# isl-test.net
KiCad netlist of a schematic drawn in EAGLE
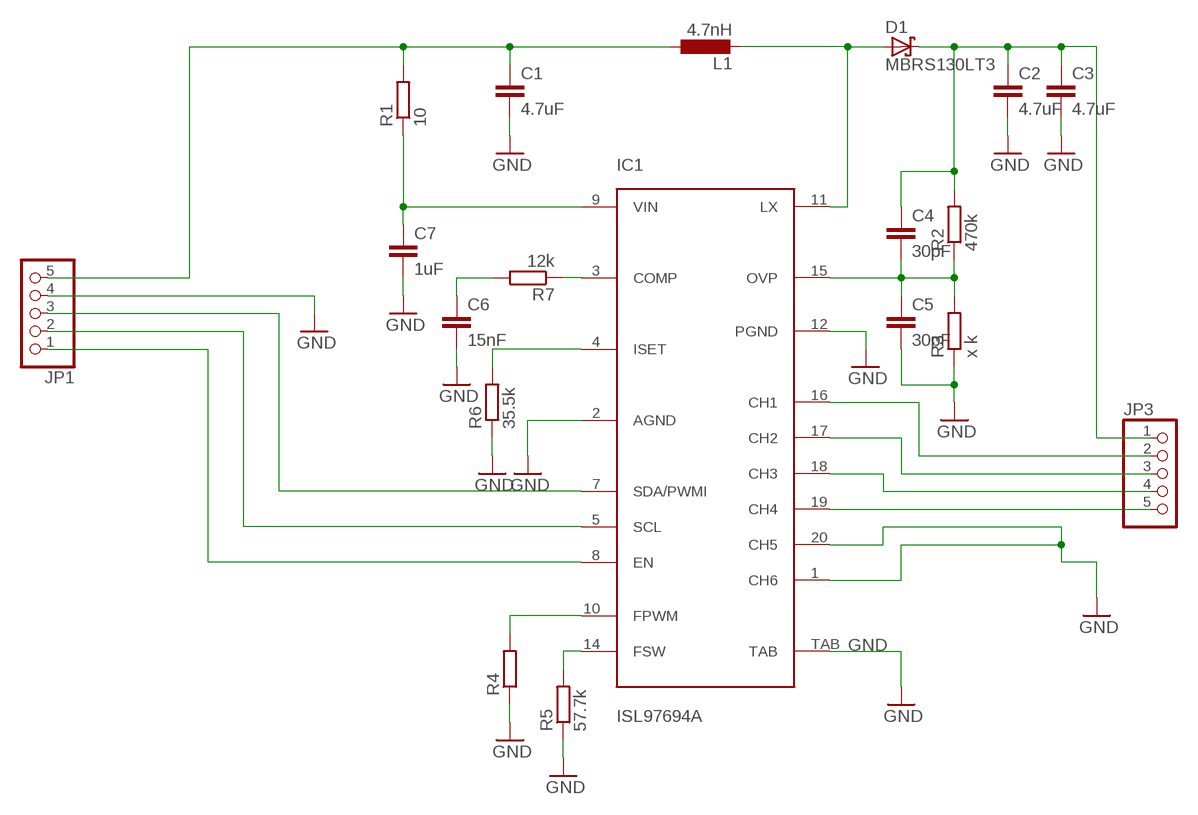
[diagram p0: schematic, sheet 1]

(export (version "E")
  (design (tool "Eeschema 10.0.6"))
  (components
    (comp (ref "C1")
      (value "4.7uF")
      (footprint "eagle-import:C0805")
      (libsource (lib "eagle-import") (part "C-EUC0805"))
    )
    (comp (ref "C2")
      (value "4.7uF")
      (footprint "eagle-import:C0805")
      (libsource (lib "eagle-import") (part "C-EUC0805"))
    )
    (comp (ref "C3")
      (value "4.7uF")
      (footprint "eagle-import:C0805")
      (libsource (lib "eagle-import") (part "C-EUC0805"))
    )
    (comp (ref "C4")
      (value "30pF")
      (footprint "eagle-import:C0603")
      (libsource (lib "eagle-import") (part "C-EUC0603"))
    )
    (comp (ref "C5")
      (value "30pF")
      (footprint "eagle-import:C0603")
      (libsource (lib "eagle-import") (part "C-EUC0603"))
    )
    (comp (ref "C6")
      (value "15nF")
      (footprint "eagle-import:C0603")
      (libsource (lib "eagle-import") (part "C-EUC0603"))
    )
    (comp (ref "C7")
      (value "1uF")
      (footprint "eagle-import:C0603")
      (libsource (lib "eagle-import") (part "C-EUC0603"))
    )
    (comp (ref "D1")
      (value "MBRS130LT3")
      (footprint "eagle-import:SMB")
      (libsource (lib "eagle-import") (part "MBRS130LT3"))
    )
    (comp (ref "IC1")
      (value "ISL97694A")
      (footprint "eagle-import:TQFN-20")
      (libsource (lib "eagle-import") (part "ISL97694A"))
    )
    (comp (ref "JP1")
      (value "PINHD-1X5")
      (footprint "eagle-import:1X05")
      (libsource (lib "eagle-import") (part "PINHD-1X5"))
    )
    (comp (ref "JP3")
      (value "PINHD-1X5")
      (footprint "eagle-import:1X05")
      (libsource (lib "eagle-import") (part "PINHD-1X5"))
    )
    (comp (ref "L1")
      (value "4.7nH")
      (footprint "eagle-import:L1812")
      (libsource (lib "eagle-import") (part "L-EUL1812"))
    )
    (comp (ref "R1")
      (value "10")
      (footprint "eagle-import:R0603")
      (libsource (lib "eagle-import") (part "R-EU_R0603"))
    )
    (comp (ref "R2")
      (value "470k")
      (footprint "eagle-import:R0603")
      (libsource (lib "eagle-import") (part "R-EU_R0603"))
    )
    (comp (ref "R3")
      (value "x k")
      (footprint "eagle-import:R0603")
      (libsource (lib "eagle-import") (part "R-EU_R0603"))
    )
    (comp (ref "R4")
      (value "R-EU_R0603")
      (footprint "eagle-import:R0603")
      (libsource (lib "eagle-import") (part "R-EU_R0603"))
    )
    (comp (ref "R5")
      (value "57.7k")
      (footprint "eagle-import:R0603")
      (libsource (lib "eagle-import") (part "R-EU_R0603"))
    )
    (comp (ref "R6")
      (value "35.5k")
      (footprint "eagle-import:R0603")
      (libsource (lib "eagle-import") (part "R-EU_R0603"))
    )
    (comp (ref "R7")
      (value "12k")
      (footprint "eagle-import:R0603")
      (libsource (lib "eagle-import") (part "R-EU_R0603"))
    )
  )
  (nets
    (net (code "1") (name "GND") (class "Default")
      (node (ref "C1") (pin "2") (pinfunction "2_2") (pintype "passive"))
      (node (ref "C2") (pin "2") (pinfunction "2_2") (pintype "passive"))
      (node (ref "C3") (pin "2") (pinfunction "2_2") (pintype "passive"))
      (node (ref "C5") (pin "2") (pinfunction "2_2") (pintype "passive"))
      (node (ref "C6") (pin "2") (pinfunction "2_2") (pintype "passive"))
      (node (ref "C7") (pin "2") (pinfunction "2_2") (pintype "passive"))
      (node (ref "IC1") (pin "1") (pinfunction "CH6_1") (pintype "input"))
      (node (ref "IC1") (pin "12") (pinfunction "PGND_12") (pintype "power_in"))
      (node (ref "IC1") (pin "2") (pinfunction "AGND_2") (pintype "power_in"))
      (node (ref "IC1") (pin "20") (pinfunction "CH5_20") (pintype "input"))
      (node (ref "IC1") (pin "TAB") (pinfunction "TAB_TAB") (pintype "power_in"))
      (node (ref "JP1") (pin "4") (pinfunction "4_4") (pintype "passive"))
      (node (ref "R3") (pin "1") (pinfunction "1_1") (pintype "passive"))
      (node (ref "R4") (pin "1") (pinfunction "1_1") (pintype "passive"))
      (node (ref "R5") (pin "1") (pinfunction "1_1") (pintype "passive"))
      (node (ref "R6") (pin "1") (pinfunction "1_1") (pintype "passive"))
    )
    (net (code "2") (name "Net-(C1-Pad1)") (class "Default")
      (node (ref "C1") (pin "1") (pinfunction "1_1") (pintype "passive"))
      (node (ref "JP1") (pin "5") (pinfunction "5_5") (pintype "passive"))
      (node (ref "L1") (pin "1") (pinfunction "1_1") (pintype "passive"))
      (node (ref "R1") (pin "2") (pinfunction "2_2") (pintype "passive"))
    )
    (net (code "3") (name "Net-(C2-Pad1)") (class "Default")
      (node (ref "C2") (pin "1") (pinfunction "1_1") (pintype "passive"))
      (node (ref "C3") (pin "1") (pinfunction "1_1") (pintype "passive"))
      (node (ref "C4") (pin "1") (pinfunction "1_1") (pintype "passive"))
      (node (ref "D1") (pin "C") (pinfunction "C_C") (pintype "passive"))
      (node (ref "JP3") (pin "1") (pinfunction "1_1") (pintype "passive"))
      (node (ref "R2") (pin "2") (pinfunction "2_2") (pintype "passive"))
    )
    (net (code "4") (name "Net-(C6-Pad1)") (class "Default")
      (node (ref "C6") (pin "1") (pinfunction "1_1") (pintype "passive"))
      (node (ref "R7") (pin "2") (pinfunction "2_2") (pintype "passive"))
    )
    (net (code "5") (name "Net-(IC1-CH1)") (class "Default")
      (node (ref "IC1") (pin "16") (pinfunction "CH1_16") (pintype "input"))
      (node (ref "JP3") (pin "2") (pinfunction "2_2") (pintype "passive"))
    )
    (net (code "6") (name "Net-(IC1-CH2)") (class "Default")
      (node (ref "IC1") (pin "17") (pinfunction "CH2_17") (pintype "input"))
      (node (ref "JP3") (pin "3") (pinfunction "3_3") (pintype "passive"))
    )
    (net (code "7") (name "Net-(IC1-CH3)") (class "Default")
      (node (ref "IC1") (pin "18") (pinfunction "CH3_18") (pintype "input"))
      (node (ref "JP3") (pin "4") (pinfunction "4_4") (pintype "passive"))
    )
    (net (code "8") (name "Net-(IC1-CH4)") (class "Default")
      (node (ref "IC1") (pin "19") (pinfunction "CH4_19") (pintype "input"))
      (node (ref "JP3") (pin "5") (pinfunction "5_5") (pintype "passive"))
    )
    (net (code "9") (name "Net-(IC1-COMP)") (class "Default")
      (node (ref "IC1") (pin "3") (pinfunction "COMP_3") (pintype "bidirectional"))
      (node (ref "R7") (pin "1") (pinfunction "1_1") (pintype "passive"))
    )
    (net (code "10") (name "Net-(IC1-EN)") (class "Default")
      (node (ref "IC1") (pin "8") (pinfunction "EN_8") (pintype "input"))
      (node (ref "JP1") (pin "1") (pinfunction "1_1") (pintype "passive"))
    )
    (net (code "11") (name "Net-(IC1-FPWM)") (class "Default")
      (node (ref "IC1") (pin "10") (pinfunction "FPWM_10") (pintype "bidirectional"))
      (node (ref "R4") (pin "2") (pinfunction "2_2") (pintype "passive"))
    )
    (net (code "12") (name "Net-(IC1-FSW)") (class "Default")
      (node (ref "IC1") (pin "14") (pinfunction "FSW_14") (pintype "bidirectional"))
      (node (ref "R5") (pin "2") (pinfunction "2_2") (pintype "passive"))
    )
    (net (code "13") (name "Net-(IC1-ISET)") (class "Default")
      (node (ref "IC1") (pin "4") (pinfunction "ISET_4") (pintype "bidirectional"))
      (node (ref "R6") (pin "2") (pinfunction "2_2") (pintype "passive"))
    )
    (net (code "14") (name "Net-(IC1-LX)") (class "Default")
      (node (ref "D1") (pin "A") (pinfunction "A_A") (pintype "passive"))
      (node (ref "IC1") (pin "11") (pinfunction "LX_11") (pintype "power_in"))
      (node (ref "L1") (pin "2") (pinfunction "2_2") (pintype "passive"))
    )
    (net (code "15") (name "Net-(IC1-OVP)") (class "Default")
      (node (ref "C4") (pin "2") (pinfunction "2_2") (pintype "passive"))
      (node (ref "C5") (pin "1") (pinfunction "1_1") (pintype "passive"))
      (node (ref "IC1") (pin "15") (pinfunction "OVP_15") (pintype "bidirectional"))
      (node (ref "R2") (pin "1") (pinfunction "1_1") (pintype "passive"))
      (node (ref "R3") (pin "2") (pinfunction "2_2") (pintype "passive"))
    )
    (net (code "16") (name "Net-(IC1-SCL)") (class "Default")
      (node (ref "IC1") (pin "5") (pinfunction "SCL_5") (pintype "input"))
      (node (ref "JP1") (pin "2") (pinfunction "2_2") (pintype "passive"))
    )
    (net (code "17") (name "Net-(IC1-SDA{slash}PWMI)") (class "Default")
      (node (ref "IC1") (pin "7") (pinfunction "SDA/PWMI_7") (pintype "bidirectional"))
      (node (ref "JP1") (pin "3") (pinfunction "3_3") (pintype "passive"))
    )
    (net (code "18") (name "Net-(IC1-VIN)") (class "Default")
      (node (ref "C7") (pin "1") (pinfunction "1_1") (pintype "passive"))
      (node (ref "IC1") (pin "9") (pinfunction "VIN_9") (pintype "power_in"))
      (node (ref "R1") (pin "1") (pinfunction "1_1") (pintype "passive"))
    )
  )
)
